# SCH_Project2_2025-11-12.net
KiCad netlist of a schematic drawn in EasyEDA
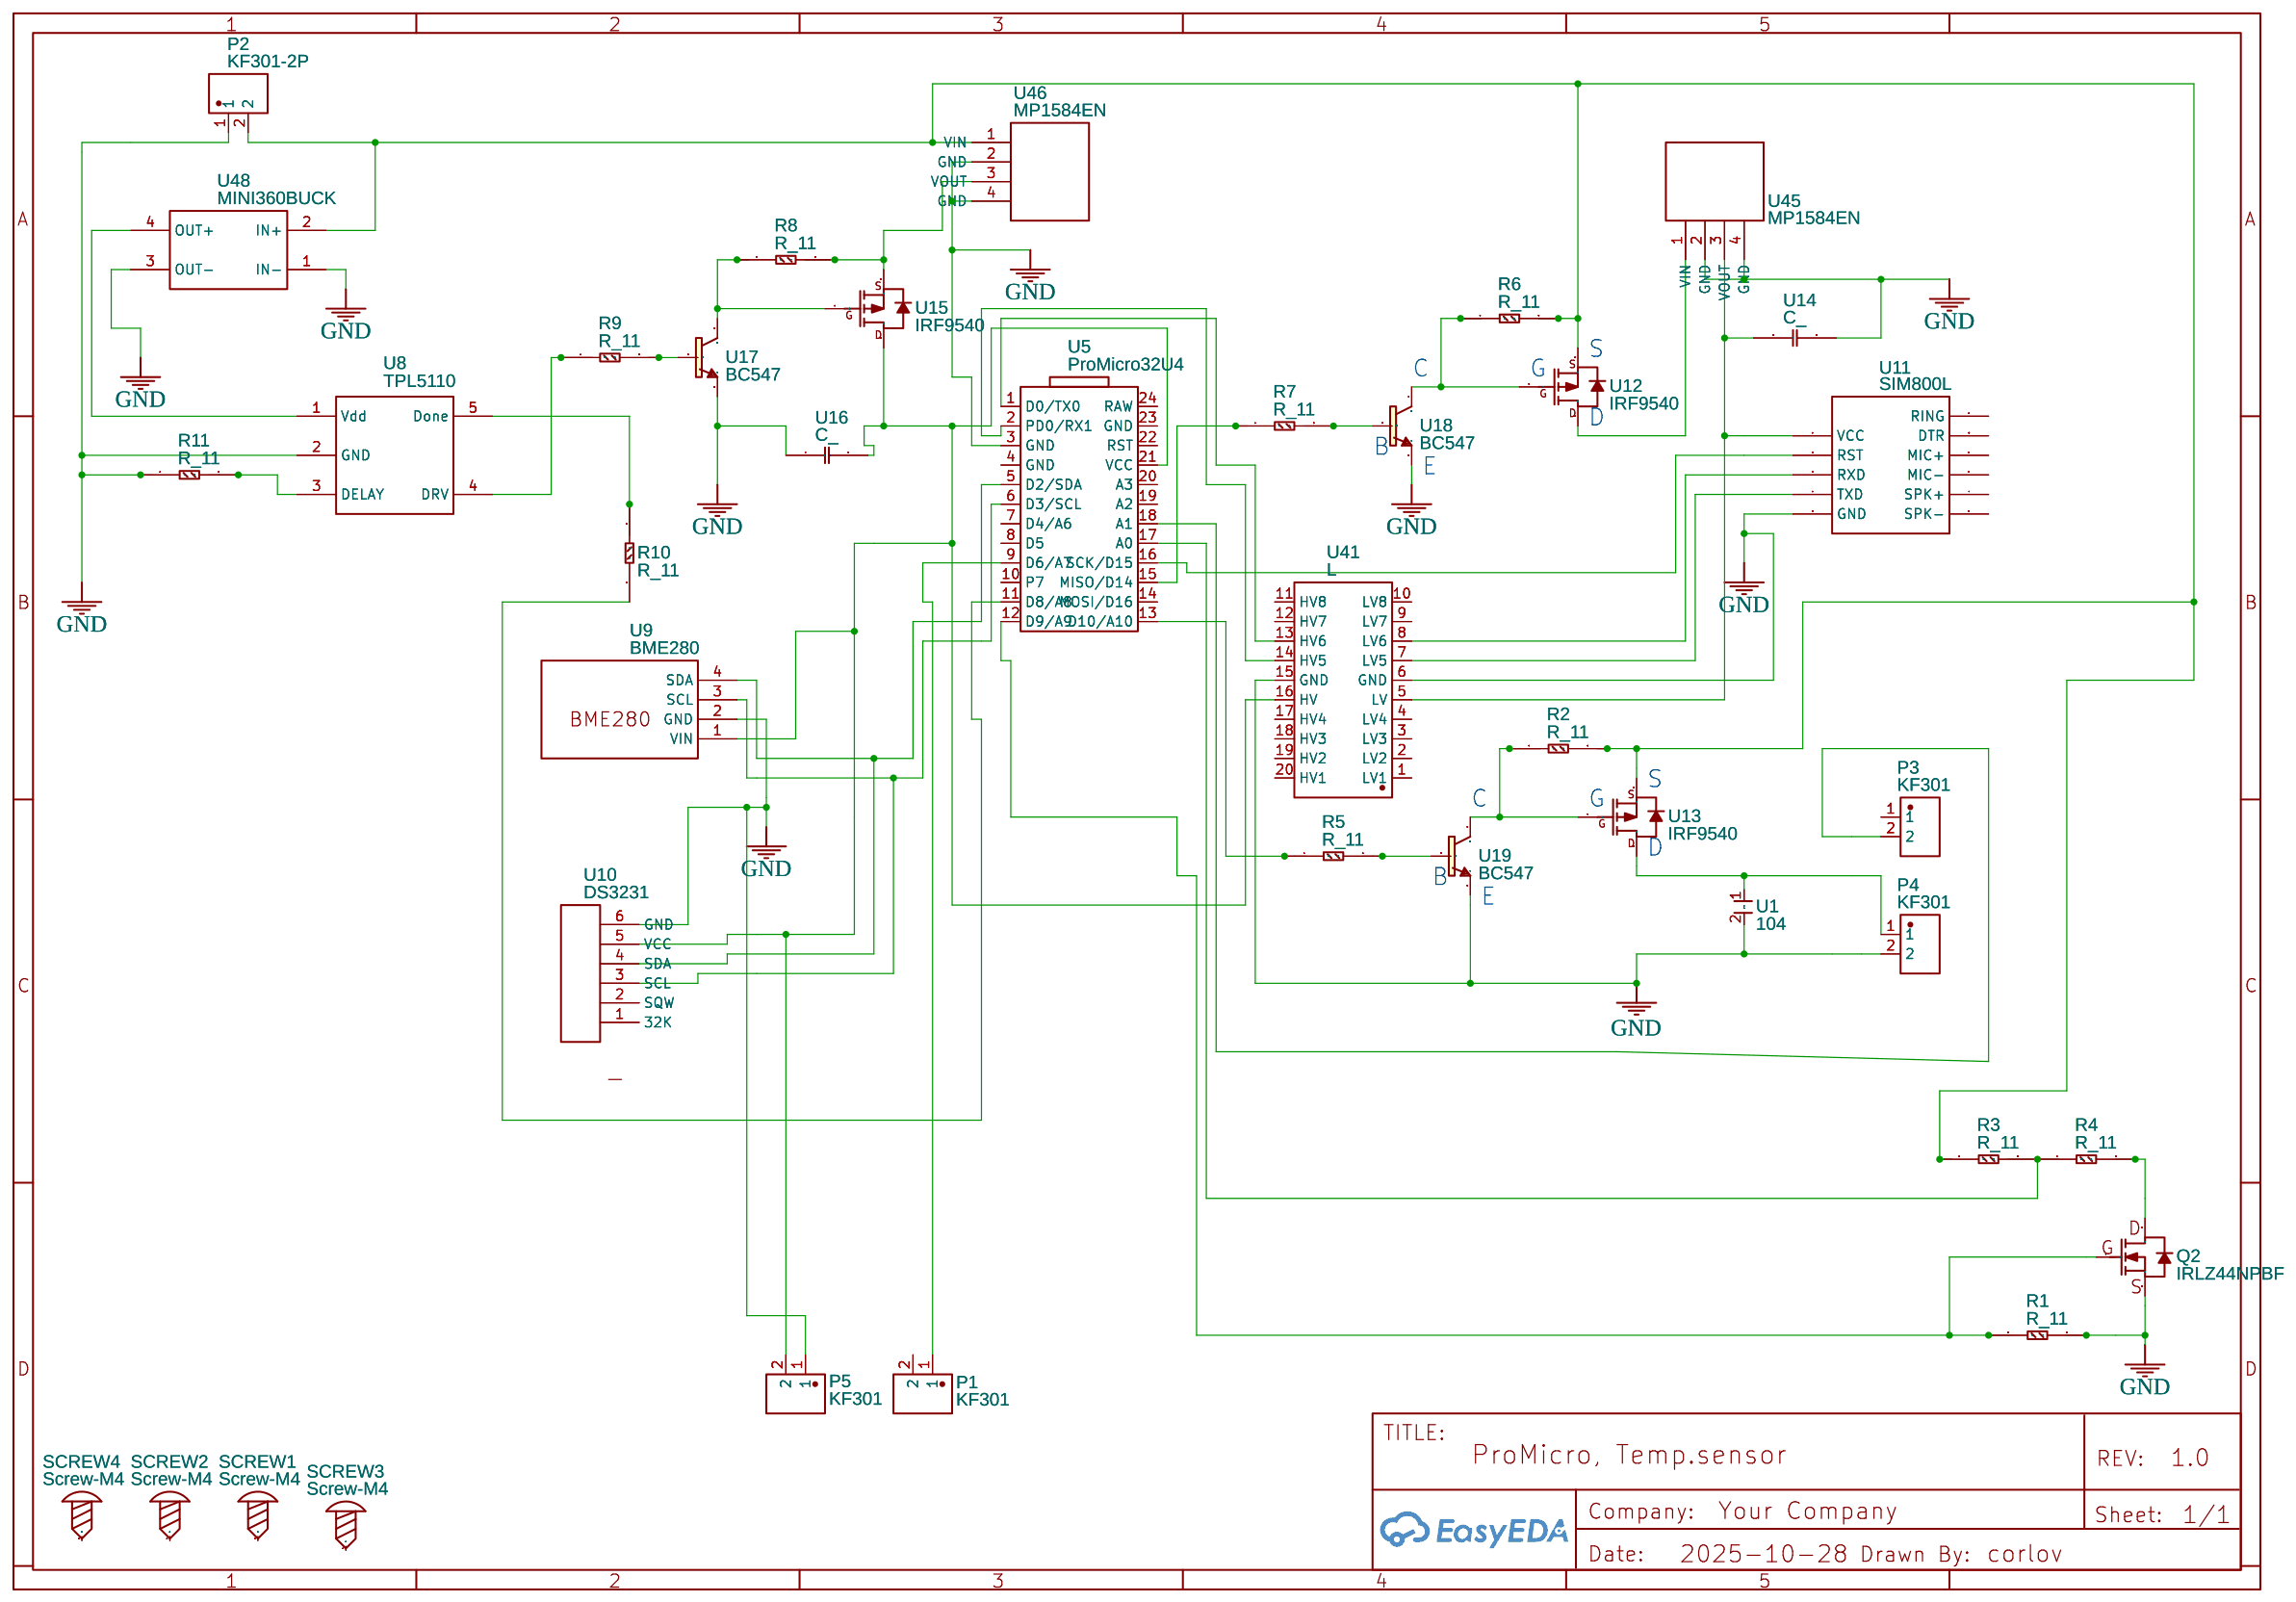
[diagram p0: Sheet_3]
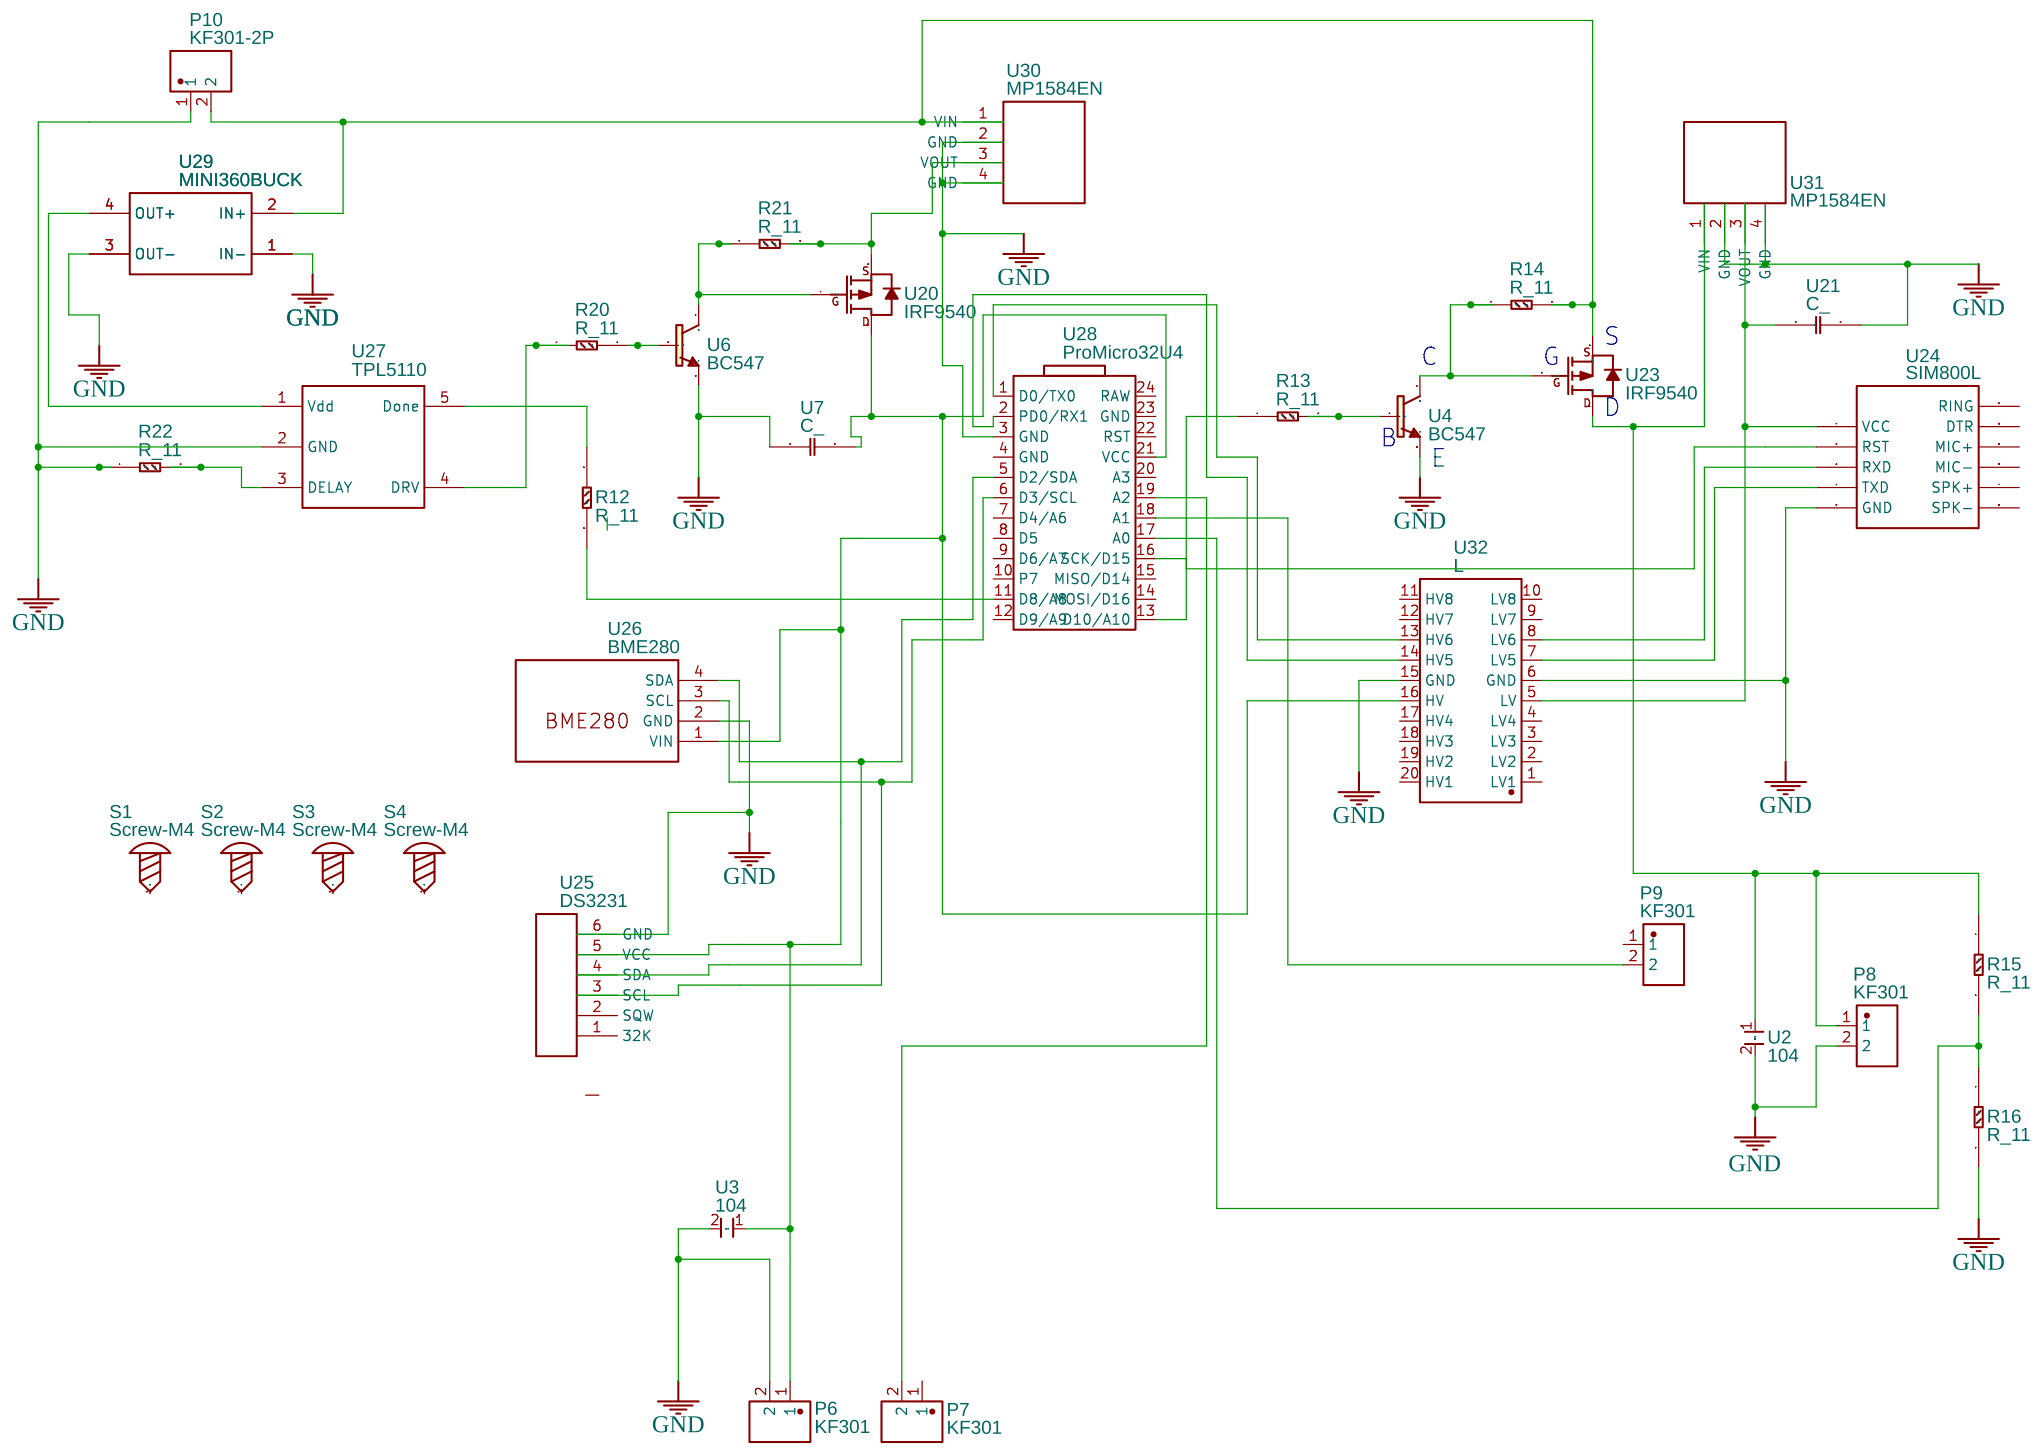
[diagram p1: Sheet_4]

(export (version "E")
  (design (tool "Eeschema 10.0.6"))
  (components
    (comp (ref "P1")
      (value "KF301")
      (fields (field (name "Manufacturer Part") "KF301-2P接线端子"))
      (libsource (lib "") (part "KF301-2P VCC Y GND"))
    )
    (comp (ref "P2")
      (value "KF301-2P")
      (fields (field (name "Manufacturer Part") "KF301-2P接线端子"))
      (libsource (lib "") (part "KF301-2P VCC Y GND_1"))
    )
    (comp (ref "P3")
      (value "KF301")
      (fields (field (name "Manufacturer Part") "KF301-2P接线端子"))
      (libsource (lib "") (part "KF301-2P VCC Y GND_2"))
    )
    (comp (ref "P4")
      (value "KF301")
      (fields (field (name "Manufacturer Part") "KF301-2P接线端子"))
      (libsource (lib "") (part "KF301-2P VCC Y GND_2"))
    )
    (comp (ref "P5")
      (value "KF301")
      (fields (field (name "Manufacturer Part") "KF301-2P接线端子"))
      (libsource (lib "") (part "KF301-2P VCC Y GND"))
    )
    (comp (ref "Q2")
      (value "IRLZ44NPBF")
      (fields (field (name "Manufacturer") "Infineon(英飞凌)"))
      (libsource (lib "") (part "IRLZ44NPBF"))
    )
    (comp (ref "R1") (value "R_11") (libsource (lib "") (part "R_")))
    (comp (ref "R2") (value "R_11") (libsource (lib "") (part "R_")))
    (comp (ref "R3") (value "R_11") (libsource (lib "") (part "R_")))
    (comp (ref "R4") (value "R_11") (libsource (lib "") (part "R_")))
    (comp (ref "R5") (value "R_11") (libsource (lib "") (part "R_")))
    (comp (ref "R6") (value "R_11") (libsource (lib "") (part "R_")))
    (comp (ref "R7") (value "R_11") (libsource (lib "") (part "R_")))
    (comp (ref "R8") (value "R_11") (libsource (lib "") (part "R_")))
    (comp (ref "R9") (value "R_11") (libsource (lib "") (part "R_")))
    (comp (ref "R10") (value "R_11") (libsource (lib "") (part "R__1")))
    (comp (ref "R11") (value "R_11") (libsource (lib "") (part "R_")))
    (comp (ref "SCREW1") (value "Screw-M4") (libsource (lib "") (part "Screw-M4")))
    (comp (ref "SCREW2") (value "Screw-M4") (libsource (lib "") (part "Screw-M4")))
    (comp (ref "SCREW3") (value "Screw-M4") (libsource (lib "") (part "Screw-M4")))
    (comp (ref "SCREW4") (value "Screw-M4") (libsource (lib "") (part "Screw-M4")))
    (comp (ref "U1")
      (value "104")
      (fields (field (name "Manufacturer") "Fe"))
      (libsource (lib "") (part "104"))
    )
    (comp (ref "U5")
      (value "ProMicro32U4")
      (fields (field (name "Manufacturer Part") "generic"))
      (libsource (lib "") (part "ProMicro32U4"))
    )
    (comp (ref "U8")
      (value "TPL5110")
      (fields (field (name "Manufacturer Part") "3435"))
      (libsource (lib "") (part "ADAFRUIT TPL5110 BREAKOUT"))
    )
    (comp (ref "U9") (value "BME280") (libsource (lib "") (part "BME280")))
    (comp (ref "U10") (value "DS3231") (libsource (lib "") (part "DS3231 upright")))
    (comp (ref "U11") (value "SIM800L") (libsource (lib "") (part "SIM800L")))
    (comp (ref "U12") (value "IRF9540") (libsource (lib "") (part "IRF9540")))
    (comp (ref "U13") (value "IRF9540") (libsource (lib "") (part "IRF9540")))
    (comp (ref "U14") (value "C_") (libsource (lib "") (part "C_")))
    (comp (ref "U15") (value "IRF9540") (libsource (lib "") (part "IRF9540")))
    (comp (ref "U16") (value "C_") (libsource (lib "") (part "C_")))
    (comp (ref "U17") (value "BC547") (libsource (lib "") (part "BC547")))
    (comp (ref "U18") (value "BC547") (libsource (lib "") (part "BC547")))
    (comp (ref "U19") (value "BC547") (libsource (lib "") (part "BC547")))
    (comp (ref "U41")
      (value "L")
      (fields (field (name "Manufacturer Part") "Level Converter 8"))
      (libsource (lib "") (part "LEVEL CONVERTER 8"))
    )
    (comp (ref "U45") (value "MP1584EN") (libsource (lib "") (part "MP1584EN_1")))
    (comp (ref "U46") (value "MP1584EN") (libsource (lib "") (part "MP1584EN")))
    (comp (ref "U48")
      (value "MINI360BUCK")
      (fields (field (name "Manufacturer Part") "Mini360"))
      (libsource (lib "") (part "MINI360BUCK"))
    )
    (comp (ref "P6")
      (value "KF301")
      (fields (field (name "Manufacturer Part") "KF301-2P接线端子"))
      (libsource (lib "") (part "KF301-2P VCC Y GND"))
    )
    (comp (ref "P7")
      (value "KF301")
      (fields (field (name "Manufacturer Part") "KF301-2P接线端子"))
      (libsource (lib "") (part "KF301-2P VCC Y GND"))
    )
    (comp (ref "P8")
      (value "KF301")
      (fields (field (name "Manufacturer Part") "KF301-2P接线端子"))
      (libsource (lib "") (part "KF301-2P VCC Y GND_1"))
    )
    (comp (ref "P9")
      (value "KF301")
      (fields (field (name "Manufacturer Part") "KF301-2P接线端子"))
      (libsource (lib "") (part "KF301-2P VCC Y GND_1"))
    )
    (comp (ref "P10")
      (value "KF301-2P")
      (fields (field (name "Manufacturer Part") "KF301-2P接线端子"))
      (libsource (lib "") (part "KF301-2P VCC Y GND_2"))
    )
    (comp (ref "R12") (value "R_11") (libsource (lib "") (part "R__1")))
    (comp (ref "R13") (value "R_11") (libsource (lib "") (part "R_")))
    (comp (ref "R14") (value "R_11") (libsource (lib "") (part "R_")))
    (comp (ref "R15") (value "R_11") (libsource (lib "") (part "R__1")))
    (comp (ref "R16") (value "R_11") (libsource (lib "") (part "R__1")))
    (comp (ref "R20") (value "R_11") (libsource (lib "") (part "R_")))
    (comp (ref "R21") (value "R_11") (libsource (lib "") (part "R_")))
    (comp (ref "R22") (value "R_11") (libsource (lib "") (part "R_")))
    (comp (ref "S1") (value "Screw-M4") (libsource (lib "") (part "Screw-M4")))
    (comp (ref "S2") (value "Screw-M4") (libsource (lib "") (part "Screw-M4")))
    (comp (ref "S3") (value "Screw-M4") (libsource (lib "") (part "Screw-M4")))
    (comp (ref "S4") (value "Screw-M4") (libsource (lib "") (part "Screw-M4")))
    (comp (ref "U2")
      (value "104")
      (fields (field (name "Manufacturer") "Fe"))
      (libsource (lib "") (part "104_1"))
    )
    (comp (ref "U3")
      (value "104")
      (fields (field (name "Manufacturer") "Fe"))
      (libsource (lib "") (part "104"))
    )
    (comp (ref "U4") (value "BC547") (libsource (lib "") (part "BC547")))
    (comp (ref "U6") (value "BC547") (libsource (lib "") (part "BC547")))
    (comp (ref "U7") (value "C_") (libsource (lib "") (part "C_")))
    (comp (ref "U20") (value "IRF9540") (libsource (lib "") (part "IRF9540")))
    (comp (ref "U21") (value "C_") (libsource (lib "") (part "C_")))
    (comp (ref "U23") (value "IRF9540") (libsource (lib "") (part "IRF9540")))
    (comp (ref "U24") (value "SIM800L") (libsource (lib "") (part "SIM800L")))
    (comp (ref "U25") (value "DS3231") (libsource (lib "") (part "DS3231 upright")))
    (comp (ref "U26") (value "BME280") (libsource (lib "") (part "BME280")))
    (comp (ref "U27")
      (value "TPL5110")
      (fields (field (name "Manufacturer Part") "3435"))
      (libsource (lib "") (part "ADAFRUIT TPL5110 BREAKOUT"))
    )
    (comp (ref "U28")
      (value "ProMicro32U4")
      (fields (field (name "Manufacturer Part") "generic"))
      (libsource (lib "") (part "ProMicro32U4"))
    )
    (comp (ref "U29")
      (value "MINI360BUCK")
      (fields (field (name "Manufacturer Part") "Mini360"))
      (libsource (lib "") (part "MINI360BUCK"))
    )
    (comp (ref "U30") (value "MP1584EN") (libsource (lib "") (part "MP1584EN_1")))
    (comp (ref "U31") (value "MP1584EN") (libsource (lib "") (part "MP1584EN")))
    (comp (ref "U32")
      (value "L")
      (fields (field (name "Manufacturer Part") "Level Converter 8"))
      (libsource (lib "") (part "LEVEL CONVERTER 8"))
    )
  )
  (nets
    (net (code "1") (name "GND") (class "Default")
      (node (ref "P10") (pin "1") (pinfunction "1_1") (pintype "unspecified"))
      (node (ref "P2") (pin "1") (pinfunction "1_1") (pintype "unspecified"))
      (node (ref "P4") (pin "2") (pinfunction "2_2") (pintype "unspecified"))
      (node (ref "P5") (pin "1") (pinfunction "1_1") (pintype "unspecified"))
      (node (ref "P6") (pin "2") (pinfunction "2_2") (pintype "unspecified"))
      (node (ref "P8") (pin "2") (pinfunction "2_2") (pintype "unspecified"))
      (node (ref "Q2") (pin "3") (pinfunction "S_3") (pintype "unspecified"))
      (node (ref "R1") (pin "2") (pinfunction "2_2") (pintype "unspecified"))
      (node (ref "R11") (pin "1") (pinfunction "1_1") (pintype "unspecified"))
      (node (ref "R16") (pin "2") (pinfunction "2_2") (pintype "unspecified"))
      (node (ref "R22") (pin "1") (pinfunction "1_1") (pintype "unspecified"))
      (node (ref "U1") (pin "2") (pinfunction "2_2") (pintype "unspecified"))
      (node (ref "U10") (pin "6") (pinfunction "GND_6") (pintype "unspecified"))
      (node (ref "U11") (pin "5") (pinfunction "GND_5") (pintype "unspecified"))
      (node (ref "U14") (pin "2") (pinfunction "2_2") (pintype "unspecified"))
      (node (ref "U16") (pin "1") (pinfunction "1_1") (pintype "unspecified"))
      (node (ref "U17") (pin "3") (pinfunction "E_3") (pintype "unspecified"))
      (node (ref "U18") (pin "3") (pinfunction "E_3") (pintype "unspecified"))
      (node (ref "U19") (pin "3") (pinfunction "E_3") (pintype "unspecified"))
      (node (ref "U2") (pin "2") (pinfunction "2_2") (pintype "unspecified"))
      (node (ref "U21") (pin "2") (pinfunction "2_2") (pintype "unspecified"))
      (node (ref "U24") (pin "5") (pinfunction "GND_5") (pintype "unspecified"))
      (node (ref "U25") (pin "6") (pinfunction "GND_6") (pintype "unspecified"))
      (node (ref "U26") (pin "2") (pinfunction "GND_2") (pintype "unspecified"))
      (node (ref "U27") (pin "2") (pinfunction "GND_2") (pintype "unspecified"))
      (node (ref "U28") (pin "3") (pinfunction "GND_3") (pintype "unspecified"))
      (node (ref "U29") (pin "1") (pinfunction "IN-_1") (pintype "unspecified"))
      (node (ref "U29") (pin "3") (pinfunction "OUT-_3") (pintype "unspecified"))
      (node (ref "U3") (pin "2") (pinfunction "2_2") (pintype "unspecified"))
      (node (ref "U30") (pin "2") (pinfunction "GND_2") (pintype "unspecified"))
      (node (ref "U30") (pin "4") (pinfunction "GND_4") (pintype "unspecified"))
      (node (ref "U31") (pin "2") (pinfunction "GND_2") (pintype "unspecified"))
      (node (ref "U31") (pin "4") (pinfunction "GND_4") (pintype "unspecified"))
      (node (ref "U32") (pin "15") (pinfunction "GND_15") (pintype "unspecified"))
      (node (ref "U32") (pin "6") (pinfunction "GND_6") (pintype "unspecified"))
      (node (ref "U4") (pin "3") (pinfunction "E_3") (pintype "unspecified"))
      (node (ref "U41") (pin "15") (pinfunction "GND_15") (pintype "unspecified"))
      (node (ref "U41") (pin "6") (pinfunction "GND_6") (pintype "unspecified"))
      (node (ref "U45") (pin "2") (pinfunction "GND_2") (pintype "unspecified"))
      (node (ref "U45") (pin "4") (pinfunction "GND_4") (pintype "unspecified"))
      (node (ref "U46") (pin "2") (pinfunction "GND_2") (pintype "unspecified"))
      (node (ref "U46") (pin "4") (pinfunction "GND_4") (pintype "unspecified"))
      (node (ref "U48") (pin "1") (pinfunction "IN-_1") (pintype "unspecified"))
      (node (ref "U48") (pin "3") (pinfunction "OUT-_3") (pintype "unspecified"))
      (node (ref "U5") (pin "3") (pinfunction "GND_3") (pintype "unspecified"))
      (node (ref "U6") (pin "3") (pinfunction "E_3") (pintype "unspecified"))
      (node (ref "U7") (pin "1") (pinfunction "1_1") (pintype "unspecified"))
      (node (ref "U8") (pin "2") (pinfunction "GND_2") (pintype "unspecified"))
      (node (ref "U9") (pin "2") (pinfunction "GND_2") (pintype "unspecified"))
    )
    (net (code "2") (name "Net-(Q2-D)") (class "Default")
      (node (ref "Q2") (pin "2") (pinfunction "D_2") (pintype "unspecified"))
      (node (ref "R4") (pin "2") (pinfunction "2_2") (pintype "unspecified"))
    )
    (net (code "3") (name "Net-(Q2-G)") (class "Default")
      (node (ref "Q2") (pin "1") (pinfunction "G_1") (pintype "unspecified"))
      (node (ref "R1") (pin "1") (pinfunction "1_1") (pintype "unspecified"))
      (node (ref "U5") (pin "12") (pinfunction "D9/A9_12") (pintype "unspecified"))
    )
    (net (code "4") (name "Net-(U4-B)") (class "Default")
      (node (ref "R13") (pin "2") (pinfunction "2_2") (pintype "unspecified"))
      (node (ref "U4") (pin "2") (pinfunction "B_2") (pintype "unspecified"))
    )
    (net (code "5") (name "Net-(U5-A0)") (class "Default")
      (node (ref "R3") (pin "2") (pinfunction "2_2") (pintype "unspecified"))
      (node (ref "R4") (pin "1") (pinfunction "1_1") (pintype "unspecified"))
      (node (ref "U5") (pin "17") (pinfunction "A0_17") (pintype "unspecified"))
    )
    (net (code "6") (name "Net-(U5-A1)") (class "Default")
      (node (ref "P3") (pin "2") (pinfunction "2_2") (pintype "unspecified"))
      (node (ref "U5") (pin "18") (pinfunction "A1_18") (pintype "unspecified"))
    )
    (net (code "7") (name "Net-(U5-D6{slash}A7)") (class "Default")
      (node (ref "P1") (pin "1") (pinfunction "1_1") (pintype "unspecified"))
      (node (ref "U5") (pin "9") (pinfunction "D6/A7_9") (pintype "unspecified"))
    )
    (net (code "8") (name "Net-(U5-D8{slash}A8)") (class "Default")
      (node (ref "R10") (pin "2") (pinfunction "2_2") (pintype "unspecified"))
      (node (ref "U5") (pin "11") (pinfunction "D8/A8_11") (pintype "unspecified"))
    )
    (net (code "9") (name "Net-(U5-D10{slash}A10)") (class "Default")
      (node (ref "R5") (pin "1") (pinfunction "1_1") (pintype "unspecified"))
      (node (ref "U5") (pin "13") (pinfunction "D10/A10_13") (pintype "unspecified"))
    )
    (net (code "10") (name "Net-(U5-MISO{slash}D14)") (class "Default")
      (node (ref "R7") (pin "1") (pinfunction "1_1") (pintype "unspecified"))
      (node (ref "U5") (pin "15") (pinfunction "MISO/D14_15") (pintype "unspecified"))
    )
    (net (code "11") (name "Net-(U6-B)") (class "Default")
      (node (ref "R20") (pin "2") (pinfunction "2_2") (pintype "unspecified"))
      (node (ref "U6") (pin "2") (pinfunction "B_2") (pintype "unspecified"))
    )
    (net (code "12") (name "Net-(U8-DELAY)") (class "Default")
      (node (ref "R11") (pin "2") (pinfunction "2_2") (pintype "unspecified"))
      (node (ref "U8") (pin "3") (pinfunction "DELAY_3") (pintype "unspecified"))
    )
    (net (code "13") (name "Net-(U8-DRV)") (class "Default")
      (node (ref "R9") (pin "1") (pinfunction "1_1") (pintype "unspecified"))
      (node (ref "U8") (pin "4") (pinfunction "DRV_4") (pintype "unspecified"))
    )
    (net (code "14") (name "Net-(U8-Done)") (class "Default")
      (node (ref "R10") (pin "1") (pinfunction "1_1") (pintype "unspecified"))
      (node (ref "U8") (pin "5") (pinfunction "Done_5") (pintype "unspecified"))
    )
    (net (code "15") (name "Net-(U10-SCL)") (class "Default")
      (node (ref "U10") (pin "3") (pinfunction "SCL_3") (pintype "unspecified"))
      (node (ref "U5") (pin "6") (pinfunction "D3/SCL_6") (pintype "unspecified"))
      (node (ref "U9") (pin "3") (pinfunction "SCL_3") (pintype "unspecified"))
    )
    (net (code "16") (name "Net-(U10-SDA)") (class "Default")
      (node (ref "U10") (pin "4") (pinfunction "SDA_4") (pintype "unspecified"))
      (node (ref "U5") (pin "5") (pinfunction "D2/SDA_5") (pintype "unspecified"))
      (node (ref "U9") (pin "4") (pinfunction "SDA_4") (pintype "unspecified"))
    )
    (net (code "17") (name "Net-(U10-VCC)") (class "Default")
      (node (ref "P5") (pin "2") (pinfunction "2_2") (pintype "unspecified"))
      (node (ref "U10") (pin "5") (pinfunction "VCC_5") (pintype "unspecified"))
      (node (ref "U15") (pin "2") (pinfunction "D_2") (pintype "unspecified"))
      (node (ref "U16") (pin "2") (pinfunction "2_2") (pintype "unspecified"))
      (node (ref "U41") (pin "16") (pinfunction "HV_16") (pintype "unspecified"))
      (node (ref "U5") (pin "21") (pinfunction "VCC_21") (pintype "unspecified"))
      (node (ref "U9") (pin "1") (pinfunction "VIN_1") (pintype "unspecified"))
    )
    (net (code "18") (name "Net-(U11-RST)") (class "Default")
      (node (ref "U11") (pin "2") (pinfunction "RST_2") (pintype "unspecified"))
      (node (ref "U5") (pin "16") (pinfunction "SCK/D15_16") (pintype "unspecified"))
    )
    (net (code "19") (name "Net-(U11-RXD)") (class "Default")
      (node (ref "U11") (pin "3") (pinfunction "RXD_3") (pintype "unspecified"))
      (node (ref "U41") (pin "8") (pinfunction "LV6_8") (pintype "unspecified"))
    )
    (net (code "20") (name "Net-(U11-TXD)") (class "Default")
      (node (ref "U11") (pin "4") (pinfunction "TXD_4") (pintype "unspecified"))
      (node (ref "U41") (pin "7") (pinfunction "LV5_7") (pintype "unspecified"))
    )
    (net (code "21") (name "Net-(U11-VCC)") (class "Default")
      (node (ref "U11") (pin "1") (pinfunction "VCC_1") (pintype "unspecified"))
      (node (ref "U14") (pin "1") (pinfunction "1_1") (pintype "unspecified"))
      (node (ref "U41") (pin "5") (pinfunction "LV_5") (pintype "unspecified"))
      (node (ref "U45") (pin "3") (pinfunction "VOUT_3") (pintype "unspecified"))
    )
    (net (code "22") (name "Net-(U12-D)") (class "Default")
      (node (ref "U12") (pin "2") (pinfunction "D_2") (pintype "unspecified"))
      (node (ref "U45") (pin "1") (pinfunction "VIN_1") (pintype "unspecified"))
    )
    (net (code "23") (name "Net-(U12-G)") (class "Default")
      (node (ref "R6") (pin "1") (pinfunction "1_1") (pintype "unspecified"))
      (node (ref "U12") (pin "1") (pinfunction "G_1") (pintype "unspecified"))
      (node (ref "U18") (pin "1") (pinfunction "C_1") (pintype "unspecified"))
    )
    (net (code "24") (name "Net-(U12-S)") (class "Default")
      (node (ref "P2") (pin "2") (pinfunction "2_2") (pintype "unspecified"))
      (node (ref "R2") (pin "2") (pinfunction "2_2") (pintype "unspecified"))
      (node (ref "R3") (pin "1") (pinfunction "1_1") (pintype "unspecified"))
      (node (ref "R6") (pin "2") (pinfunction "2_2") (pintype "unspecified"))
      (node (ref "U12") (pin "3") (pinfunction "S_3") (pintype "unspecified"))
      (node (ref "U13") (pin "3") (pinfunction "S_3") (pintype "unspecified"))
      (node (ref "U46") (pin "1") (pinfunction "VIN_1") (pintype "unspecified"))
      (node (ref "U48") (pin "2") (pinfunction "IN+_2") (pintype "unspecified"))
    )
    (net (code "25") (name "Net-(U13-D)") (class "Default")
      (node (ref "P4") (pin "1") (pinfunction "1_1") (pintype "unspecified"))
      (node (ref "U1") (pin "1") (pinfunction "1_1") (pintype "unspecified"))
      (node (ref "U13") (pin "2") (pinfunction "D_2") (pintype "unspecified"))
    )
    (net (code "26") (name "Net-(U13-G)") (class "Default")
      (node (ref "R2") (pin "1") (pinfunction "1_1") (pintype "unspecified"))
      (node (ref "U13") (pin "1") (pinfunction "G_1") (pintype "unspecified"))
      (node (ref "U19") (pin "1") (pinfunction "C_1") (pintype "unspecified"))
    )
    (net (code "27") (name "Net-(U15-G)") (class "Default")
      (node (ref "R8") (pin "1") (pinfunction "1_1") (pintype "unspecified"))
      (node (ref "U15") (pin "1") (pinfunction "G_1") (pintype "unspecified"))
      (node (ref "U17") (pin "1") (pinfunction "C_1") (pintype "unspecified"))
    )
    (net (code "28") (name "Net-(U15-S)") (class "Default")
      (node (ref "R8") (pin "2") (pinfunction "2_2") (pintype "unspecified"))
      (node (ref "U15") (pin "3") (pinfunction "S_3") (pintype "unspecified"))
      (node (ref "U46") (pin "3") (pinfunction "VOUT_3") (pintype "unspecified"))
    )
    (net (code "29") (name "Net-(U17-B)") (class "Default")
      (node (ref "R9") (pin "2") (pinfunction "2_2") (pintype "unspecified"))
      (node (ref "U17") (pin "2") (pinfunction "B_2") (pintype "unspecified"))
    )
    (net (code "30") (name "Net-(U18-B)") (class "Default")
      (node (ref "R7") (pin "2") (pinfunction "2_2") (pintype "unspecified"))
      (node (ref "U18") (pin "2") (pinfunction "B_2") (pintype "unspecified"))
    )
    (net (code "31") (name "Net-(U19-B)") (class "Default")
      (node (ref "R5") (pin "2") (pinfunction "2_2") (pintype "unspecified"))
      (node (ref "U19") (pin "2") (pinfunction "B_2") (pintype "unspecified"))
    )
    (net (code "32") (name "Net-(U20-D)") (class "Default")
      (node (ref "P6") (pin "1") (pinfunction "1_1") (pintype "unspecified"))
      (node (ref "U20") (pin "2") (pinfunction "D_2") (pintype "unspecified"))
      (node (ref "U25") (pin "5") (pinfunction "VCC_5") (pintype "unspecified"))
      (node (ref "U26") (pin "1") (pinfunction "VIN_1") (pintype "unspecified"))
      (node (ref "U28") (pin "21") (pinfunction "VCC_21") (pintype "unspecified"))
      (node (ref "U3") (pin "1") (pinfunction "1_1") (pintype "unspecified"))
      (node (ref "U32") (pin "16") (pinfunction "HV_16") (pintype "unspecified"))
      (node (ref "U7") (pin "2") (pinfunction "2_2") (pintype "unspecified"))
    )
    (net (code "33") (name "Net-(U20-G)") (class "Default")
      (node (ref "R21") (pin "1") (pinfunction "1_1") (pintype "unspecified"))
      (node (ref "U20") (pin "1") (pinfunction "G_1") (pintype "unspecified"))
      (node (ref "U6") (pin "1") (pinfunction "C_1") (pintype "unspecified"))
    )
    (net (code "34") (name "Net-(U20-S)") (class "Default")
      (node (ref "R21") (pin "2") (pinfunction "2_2") (pintype "unspecified"))
      (node (ref "U20") (pin "3") (pinfunction "S_3") (pintype "unspecified"))
      (node (ref "U30") (pin "3") (pinfunction "VOUT_3") (pintype "unspecified"))
    )
    (net (code "35") (name "Net-(U23-D)") (class "Default")
      (node (ref "P8") (pin "1") (pinfunction "1_1") (pintype "unspecified"))
      (node (ref "R15") (pin "1") (pinfunction "1_1") (pintype "unspecified"))
      (node (ref "U2") (pin "1") (pinfunction "1_1") (pintype "unspecified"))
      (node (ref "U23") (pin "2") (pinfunction "D_2") (pintype "unspecified"))
      (node (ref "U31") (pin "1") (pinfunction "VIN_1") (pintype "unspecified"))
    )
    (net (code "36") (name "Net-(U23-G)") (class "Default")
      (node (ref "R14") (pin "1") (pinfunction "1_1") (pintype "unspecified"))
      (node (ref "U23") (pin "1") (pinfunction "G_1") (pintype "unspecified"))
      (node (ref "U4") (pin "1") (pinfunction "C_1") (pintype "unspecified"))
    )
    (net (code "37") (name "Net-(U23-S)") (class "Default")
      (node (ref "P10") (pin "2") (pinfunction "2_2") (pintype "unspecified"))
      (node (ref "R14") (pin "2") (pinfunction "2_2") (pintype "unspecified"))
      (node (ref "U23") (pin "3") (pinfunction "S_3") (pintype "unspecified"))
      (node (ref "U29") (pin "2") (pinfunction "IN+_2") (pintype "unspecified"))
      (node (ref "U30") (pin "1") (pinfunction "VIN_1") (pintype "unspecified"))
    )
    (net (code "38") (name "Net-(U24-RST)") (class "Default")
      (node (ref "U24") (pin "2") (pinfunction "RST_2") (pintype "unspecified"))
      (node (ref "U28") (pin "16") (pinfunction "SCK/D15_16") (pintype "unspecified"))
    )
    (net (code "39") (name "Net-(U24-RXD)") (class "Default")
      (node (ref "U24") (pin "3") (pinfunction "RXD_3") (pintype "unspecified"))
      (node (ref "U32") (pin "8") (pinfunction "LV6_8") (pintype "unspecified"))
    )
    (net (code "40") (name "Net-(U24-TXD)") (class "Default")
      (node (ref "U24") (pin "4") (pinfunction "TXD_4") (pintype "unspecified"))
      (node (ref "U32") (pin "7") (pinfunction "LV5_7") (pintype "unspecified"))
    )
    (net (code "41") (name "Net-(U24-VCC)") (class "Default")
      (node (ref "U21") (pin "1") (pinfunction "1_1") (pintype "unspecified"))
      (node (ref "U24") (pin "1") (pinfunction "VCC_1") (pintype "unspecified"))
      (node (ref "U31") (pin "3") (pinfunction "VOUT_3") (pintype "unspecified"))
      (node (ref "U32") (pin "5") (pinfunction "LV_5") (pintype "unspecified"))
    )
    (net (code "42") (name "Net-(U25-SCL)") (class "Default")
      (node (ref "U25") (pin "3") (pinfunction "SCL_3") (pintype "unspecified"))
      (node (ref "U26") (pin "3") (pinfunction "SCL_3") (pintype "unspecified"))
      (node (ref "U28") (pin "6") (pinfunction "D3/SCL_6") (pintype "unspecified"))
    )
    (net (code "43") (name "Net-(U25-SDA)") (class "Default")
      (node (ref "U25") (pin "4") (pinfunction "SDA_4") (pintype "unspecified"))
      (node (ref "U26") (pin "4") (pinfunction "SDA_4") (pintype "unspecified"))
      (node (ref "U28") (pin "5") (pinfunction "D2/SDA_5") (pintype "unspecified"))
    )
    (net (code "44") (name "Net-(U27-DELAY)") (class "Default")
      (node (ref "R22") (pin "2") (pinfunction "2_2") (pintype "unspecified"))
      (node (ref "U27") (pin "3") (pinfunction "DELAY_3") (pintype "unspecified"))
    )
    (net (code "45") (name "Net-(U27-DRV)") (class "Default")
      (node (ref "R20") (pin "1") (pinfunction "1_1") (pintype "unspecified"))
      (node (ref "U27") (pin "4") (pinfunction "DRV_4") (pintype "unspecified"))
    )
    (net (code "46") (name "Net-(U27-Done)") (class "Default")
      (node (ref "R12") (pin "1") (pinfunction "1_1") (pintype "unspecified"))
      (node (ref "U27") (pin "5") (pinfunction "Done_5") (pintype "unspecified"))
    )
    (net (code "47") (name "Net-(U27-Vdd)") (class "Default")
      (node (ref "U27") (pin "1") (pinfunction "Vdd_1") (pintype "unspecified"))
      (node (ref "U29") (pin "4") (pinfunction "OUT+_4") (pintype "unspecified"))
    )
    (net (code "48") (name "Net-(U28-A0)") (class "Default")
      (node (ref "R15") (pin "2") (pinfunction "2_2") (pintype "unspecified"))
      (node (ref "R16") (pin "1") (pinfunction "1_1") (pintype "unspecified"))
      (node (ref "U28") (pin "17") (pinfunction "A0_17") (pintype "unspecified"))
    )
    (net (code "49") (name "Net-(U28-A1)") (class "Default")
      (node (ref "P9") (pin "2") (pinfunction "2_2") (pintype "unspecified"))
      (node (ref "U28") (pin "18") (pinfunction "A1_18") (pintype "unspecified"))
    )
    (net (code "50") (name "Net-(U28-A2)") (class "Default")
      (node (ref "P7") (pin "2") (pinfunction "2_2") (pintype "unspecified"))
      (node (ref "U28") (pin "19") (pinfunction "A2_19") (pintype "unspecified"))
    )
    (net (code "51") (name "Net-(U28-D0{slash}TX0)") (class "Default")
      (node (ref "U28") (pin "1") (pinfunction "D0/TX0_1") (pintype "unspecified"))
      (node (ref "U32") (pin "13") (pinfunction "HV6_13") (pintype "unspecified"))
    )
    (net (code "52") (name "Net-(U28-D8{slash}A8)") (class "Default")
      (node (ref "R12") (pin "2") (pinfunction "2_2") (pintype "unspecified"))
      (node (ref "U28") (pin "11") (pinfunction "D8/A8_11") (pintype "unspecified"))
    )
    (net (code "53") (name "Net-(U28-D10{slash}A10)") (class "Default")
      (node (ref "R13") (pin "1") (pinfunction "1_1") (pintype "unspecified"))
      (node (ref "U28") (pin "13") (pinfunction "D10/A10_13") (pintype "unspecified"))
    )
    (net (code "54") (name "Net-(U28-PD0{slash}RX1)") (class "Default")
      (node (ref "U28") (pin "2") (pinfunction "PD0/RX1_2") (pintype "unspecified"))
      (node (ref "U32") (pin "14") (pinfunction "HV5_14") (pintype "unspecified"))
    )
    (net (code "55") (name "Net-(U41-HV5)") (class "Default")
      (node (ref "U41") (pin "14") (pinfunction "HV5_14") (pintype "unspecified"))
      (node (ref "U5") (pin "2") (pinfunction "PD0/RX1_2") (pintype "unspecified"))
    )
    (net (code "56") (name "Net-(U41-HV6)") (class "Default")
      (node (ref "U41") (pin "13") (pinfunction "HV6_13") (pintype "unspecified"))
      (node (ref "U5") (pin "1") (pinfunction "D0/TX0_1") (pintype "unspecified"))
    )
    (net (code "57") (name "Net-(U48-OUT+)") (class "Default")
      (node (ref "U48") (pin "4") (pinfunction "OUT+_4") (pintype "unspecified"))
      (node (ref "U8") (pin "1") (pinfunction "Vdd_1") (pintype "unspecified"))
    )
    (net (code "58") (name "unconnected-(P1-Pad2)") (class "Default")
      (node (ref "P1") (pin "2") (pinfunction "2_2") (pintype "unspecified"))
    )
    (net (code "59") (name "unconnected-(P3-Pad1)") (class "Default")
      (node (ref "P3") (pin "1") (pinfunction "1_1") (pintype "unspecified"))
    )
    (net (code "60") (name "unconnected-(P7-Pad1)") (class "Default")
      (node (ref "P7") (pin "1") (pinfunction "1_1") (pintype "unspecified"))
    )
    (net (code "61") (name "unconnected-(P9-Pad1)") (class "Default")
      (node (ref "P9") (pin "1") (pinfunction "1_1") (pintype "unspecified"))
    )
    (net (code "62") (name "unconnected-(S1-Pad1)") (class "Default")
      (node (ref "S1") (pin "1") (pinfunction "1_1") (pintype "unspecified"))
    )
    (net (code "63") (name "unconnected-(S2-Pad1)") (class "Default")
      (node (ref "S2") (pin "1") (pinfunction "1_1") (pintype "unspecified"))
    )
    (net (code "64") (name "unconnected-(S3-Pad1)") (class "Default")
      (node (ref "S3") (pin "1") (pinfunction "1_1") (pintype "unspecified"))
    )
    (net (code "65") (name "unconnected-(S4-Pad1)") (class "Default")
      (node (ref "S4") (pin "1") (pinfunction "1_1") (pintype "unspecified"))
    )
    (net (code "66") (name "unconnected-(SCREW1-Pad1)") (class "Default")
      (node (ref "SCREW1") (pin "1") (pinfunction "1_1") (pintype "unspecified"))
    )
    (net (code "67") (name "unconnected-(SCREW2-Pad1)") (class "Default")
      (node (ref "SCREW2") (pin "1") (pinfunction "1_1") (pintype "unspecified"))
    )
    (net (code "68") (name "unconnected-(SCREW3-Pad1)") (class "Default")
      (node (ref "SCREW3") (pin "1") (pinfunction "1_1") (pintype "unspecified"))
    )
    (net (code "69") (name "unconnected-(SCREW4-Pad1)") (class "Default")
      (node (ref "SCREW4") (pin "1") (pinfunction "1_1") (pintype "unspecified"))
    )
    (net (code "70") (name "unconnected-(U5-A2-Pad19)") (class "Default")
      (node (ref "U5") (pin "19") (pinfunction "A2_19") (pintype "unspecified"))
    )
    (net (code "71") (name "unconnected-(U5-A3-Pad20)") (class "Default")
      (node (ref "U5") (pin "20") (pinfunction "A3_20") (pintype "unspecified"))
    )
    (net (code "72") (name "unconnected-(U5-D4{slash}A6-Pad7)") (class "Default")
      (node (ref "U5") (pin "7") (pinfunction "D4/A6_7") (pintype "unspecified"))
    )
    (net (code "73") (name "unconnected-(U5-D5-Pad8)") (class "Default")
      (node (ref "U5") (pin "8") (pinfunction "D5_8") (pintype "unspecified"))
    )
    (net (code "74") (name "unconnected-(U5-GND-Pad4)") (class "Default")
      (node (ref "U5") (pin "4") (pinfunction "GND_4") (pintype "unspecified"))
    )
    (net (code "75") (name "unconnected-(U5-GND-Pad23)") (class "Default")
      (node (ref "U5") (pin "23") (pinfunction "GND_23") (pintype "unspecified"))
    )
    (net (code "76") (name "unconnected-(U5-MOSI{slash}D16-Pad14)") (class "Default")
      (node (ref "U5") (pin "14") (pinfunction "MOSI/D16_14") (pintype "unspecified"))
    )
    (net (code "77") (name "unconnected-(U5-P7-Pad10)") (class "Default")
      (node (ref "U5") (pin "10") (pinfunction "P7_10") (pintype "unspecified"))
    )
    (net (code "78") (name "unconnected-(U5-RAW-Pad24)") (class "Default")
      (node (ref "U5") (pin "24") (pinfunction "RAW_24") (pintype "unspecified"))
    )
    (net (code "79") (name "unconnected-(U5-RST-Pad22)") (class "Default")
      (node (ref "U5") (pin "22") (pinfunction "RST_22") (pintype "unspecified"))
    )
    (net (code "80") (name "unconnected-(U10-32K-Pad1)") (class "Default")
      (node (ref "U10") (pin "1") (pinfunction "32K_1") (pintype "unspecified"))
    )
    (net (code "81") (name "unconnected-(U10-SQW-Pad2)") (class "Default")
      (node (ref "U10") (pin "2") (pinfunction "SQW_2") (pintype "unspecified"))
    )
    (net (code "82") (name "unconnected-(U11-DTR-Pad10)") (class "Default")
      (node (ref "U11") (pin "10") (pinfunction "DTR_10") (pintype "unspecified"))
    )
    (net (code "83") (name "unconnected-(U11-MIC+-Pad9)") (class "Default")
      (node (ref "U11") (pin "9") (pinfunction "MIC+_9") (pintype "unspecified"))
    )
    (net (code "84") (name "unconnected-(U11-MIC--Pad8)") (class "Default")
      (node (ref "U11") (pin "8") (pinfunction "MIC-_8") (pintype "unspecified"))
    )
    (net (code "85") (name "unconnected-(U11-RING-Pad11)") (class "Default")
      (node (ref "U11") (pin "11") (pinfunction "RING_11") (pintype "unspecified"))
    )
    (net (code "86") (name "unconnected-(U11-SPK+-Pad7)") (class "Default")
      (node (ref "U11") (pin "7") (pinfunction "SPK+_7") (pintype "unspecified"))
    )
    (net (code "87") (name "unconnected-(U11-SPK--Pad6)") (class "Default")
      (node (ref "U11") (pin "6") (pinfunction "SPK-_6") (pintype "unspecified"))
    )
    (net (code "88") (name "unconnected-(U24-DTR-Pad10)") (class "Default")
      (node (ref "U24") (pin "10") (pinfunction "DTR_10") (pintype "unspecified"))
    )
    (net (code "89") (name "unconnected-(U24-MIC+-Pad9)") (class "Default")
      (node (ref "U24") (pin "9") (pinfunction "MIC+_9") (pintype "unspecified"))
    )
    (net (code "90") (name "unconnected-(U24-MIC--Pad8)") (class "Default")
      (node (ref "U24") (pin "8") (pinfunction "MIC-_8") (pintype "unspecified"))
    )
    (net (code "91") (name "unconnected-(U24-RING-Pad11)") (class "Default")
      (node (ref "U24") (pin "11") (pinfunction "RING_11") (pintype "unspecified"))
    )
    (net (code "92") (name "unconnected-(U24-SPK+-Pad7)") (class "Default")
      (node (ref "U24") (pin "7") (pinfunction "SPK+_7") (pintype "unspecified"))
    )
    (net (code "93") (name "unconnected-(U24-SPK--Pad6)") (class "Default")
      (node (ref "U24") (pin "6") (pinfunction "SPK-_6") (pintype "unspecified"))
    )
    (net (code "94") (name "unconnected-(U25-32K-Pad1)") (class "Default")
      (node (ref "U25") (pin "1") (pinfunction "32K_1") (pintype "unspecified"))
    )
    (net (code "95") (name "unconnected-(U25-SQW-Pad2)") (class "Default")
      (node (ref "U25") (pin "2") (pinfunction "SQW_2") (pintype "unspecified"))
    )
    (net (code "96") (name "unconnected-(U28-A3-Pad20)") (class "Default")
      (node (ref "U28") (pin "20") (pinfunction "A3_20") (pintype "unspecified"))
    )
    (net (code "97") (name "unconnected-(U28-D4{slash}A6-Pad7)") (class "Default")
      (node (ref "U28") (pin "7") (pinfunction "D4/A6_7") (pintype "unspecified"))
    )
    (net (code "98") (name "unconnected-(U28-D5-Pad8)") (class "Default")
      (node (ref "U28") (pin "8") (pinfunction "D5_8") (pintype "unspecified"))
    )
    (net (code "99") (name "unconnected-(U28-D6{slash}A7-Pad9)") (class "Default")
      (node (ref "U28") (pin "9") (pinfunction "D6/A7_9") (pintype "unspecified"))
    )
    (net (code "100") (name "unconnected-(U28-D9{slash}A9-Pad12)") (class "Default")
      (node (ref "U28") (pin "12") (pinfunction "D9/A9_12") (pintype "unspecified"))
    )
    (net (code "101") (name "unconnected-(U28-GND-Pad4)") (class "Default")
      (node (ref "U28") (pin "4") (pinfunction "GND_4") (pintype "unspecified"))
    )
    (net (code "102") (name "unconnected-(U28-GND-Pad23)") (class "Default")
      (node (ref "U28") (pin "23") (pinfunction "GND_23") (pintype "unspecified"))
    )
    (net (code "103") (name "unconnected-(U28-MISO{slash}D14-Pad15)") (class "Default")
      (node (ref "U28") (pin "15") (pinfunction "MISO/D14_15") (pintype "unspecified"))
    )
    (net (code "104") (name "unconnected-(U28-MOSI{slash}D16-Pad14)") (class "Default")
      (node (ref "U28") (pin "14") (pinfunction "MOSI/D16_14") (pintype "unspecified"))
    )
    (net (code "105") (name "unconnected-(U28-P7-Pad10)") (class "Default")
      (node (ref "U28") (pin "10") (pinfunction "P7_10") (pintype "unspecified"))
    )
    (net (code "106") (name "unconnected-(U28-RAW-Pad24)") (class "Default")
      (node (ref "U28") (pin "24") (pinfunction "RAW_24") (pintype "unspecified"))
    )
    (net (code "107") (name "unconnected-(U28-RST-Pad22)") (class "Default")
      (node (ref "U28") (pin "22") (pinfunction "RST_22") (pintype "unspecified"))
    )
    (net (code "108") (name "unconnected-(U32-HV1-Pad20)") (class "Default")
      (node (ref "U32") (pin "20") (pinfunction "HV1_20") (pintype "unspecified"))
    )
    (net (code "109") (name "unconnected-(U32-HV2-Pad19)") (class "Default")
      (node (ref "U32") (pin "19") (pinfunction "HV2_19") (pintype "unspecified"))
    )
    (net (code "110") (name "unconnected-(U32-HV3-Pad18)") (class "Default")
      (node (ref "U32") (pin "18") (pinfunction "HV3_18") (pintype "unspecified"))
    )
    (net (code "111") (name "unconnected-(U32-HV4-Pad17)") (class "Default")
      (node (ref "U32") (pin "17") (pinfunction "HV4_17") (pintype "unspecified"))
    )
    (net (code "112") (name "unconnected-(U32-HV7-Pad12)") (class "Default")
      (node (ref "U32") (pin "12") (pinfunction "HV7_12") (pintype "unspecified"))
    )
    (net (code "113") (name "unconnected-(U32-HV8-Pad11)") (class "Default")
      (node (ref "U32") (pin "11") (pinfunction "HV8_11") (pintype "unspecified"))
    )
    (net (code "114") (name "unconnected-(U32-LV1-Pad1)") (class "Default")
      (node (ref "U32") (pin "1") (pinfunction "LV1_1") (pintype "unspecified"))
    )
    (net (code "115") (name "unconnected-(U32-LV2-Pad2)") (class "Default")
      (node (ref "U32") (pin "2") (pinfunction "LV2_2") (pintype "unspecified"))
    )
    (net (code "116") (name "unconnected-(U32-LV3-Pad3)") (class "Default")
      (node (ref "U32") (pin "3") (pinfunction "LV3_3") (pintype "unspecified"))
    )
    (net (code "117") (name "unconnected-(U32-LV4-Pad4)") (class "Default")
      (node (ref "U32") (pin "4") (pinfunction "LV4_4") (pintype "unspecified"))
    )
    (net (code "118") (name "unconnected-(U32-LV7-Pad9)") (class "Default")
      (node (ref "U32") (pin "9") (pinfunction "LV7_9") (pintype "unspecified"))
    )
    (net (code "119") (name "unconnected-(U32-LV8-Pad10)") (class "Default")
      (node (ref "U32") (pin "10") (pinfunction "LV8_10") (pintype "unspecified"))
    )
    (net (code "120") (name "unconnected-(U41-HV1-Pad20)") (class "Default")
      (node (ref "U41") (pin "20") (pinfunction "HV1_20") (pintype "unspecified"))
    )
    (net (code "121") (name "unconnected-(U41-HV2-Pad19)") (class "Default")
      (node (ref "U41") (pin "19") (pinfunction "HV2_19") (pintype "unspecified"))
    )
    (net (code "122") (name "unconnected-(U41-HV3-Pad18)") (class "Default")
      (node (ref "U41") (pin "18") (pinfunction "HV3_18") (pintype "unspecified"))
    )
    (net (code "123") (name "unconnected-(U41-HV4-Pad17)") (class "Default")
      (node (ref "U41") (pin "17") (pinfunction "HV4_17") (pintype "unspecified"))
    )
    (net (code "124") (name "unconnected-(U41-HV7-Pad12)") (class "Default")
      (node (ref "U41") (pin "12") (pinfunction "HV7_12") (pintype "unspecified"))
    )
    (net (code "125") (name "unconnected-(U41-HV8-Pad11)") (class "Default")
      (node (ref "U41") (pin "11") (pinfunction "HV8_11") (pintype "unspecified"))
    )
    (net (code "126") (name "unconnected-(U41-LV1-Pad1)") (class "Default")
      (node (ref "U41") (pin "1") (pinfunction "LV1_1") (pintype "unspecified"))
    )
    (net (code "127") (name "unconnected-(U41-LV2-Pad2)") (class "Default")
      (node (ref "U41") (pin "2") (pinfunction "LV2_2") (pintype "unspecified"))
    )
    (net (code "128") (name "unconnected-(U41-LV3-Pad3)") (class "Default")
      (node (ref "U41") (pin "3") (pinfunction "LV3_3") (pintype "unspecified"))
    )
    (net (code "129") (name "unconnected-(U41-LV4-Pad4)") (class "Default")
      (node (ref "U41") (pin "4") (pinfunction "LV4_4") (pintype "unspecified"))
    )
    (net (code "130") (name "unconnected-(U41-LV7-Pad9)") (class "Default")
      (node (ref "U41") (pin "9") (pinfunction "LV7_9") (pintype "unspecified"))
    )
    (net (code "131") (name "unconnected-(U41-LV8-Pad10)") (class "Default")
      (node (ref "U41") (pin "10") (pinfunction "LV8_10") (pintype "unspecified"))
    )
  )
)
